# main_board.net
KiCad netlist of a schematic drawn in EAGLE
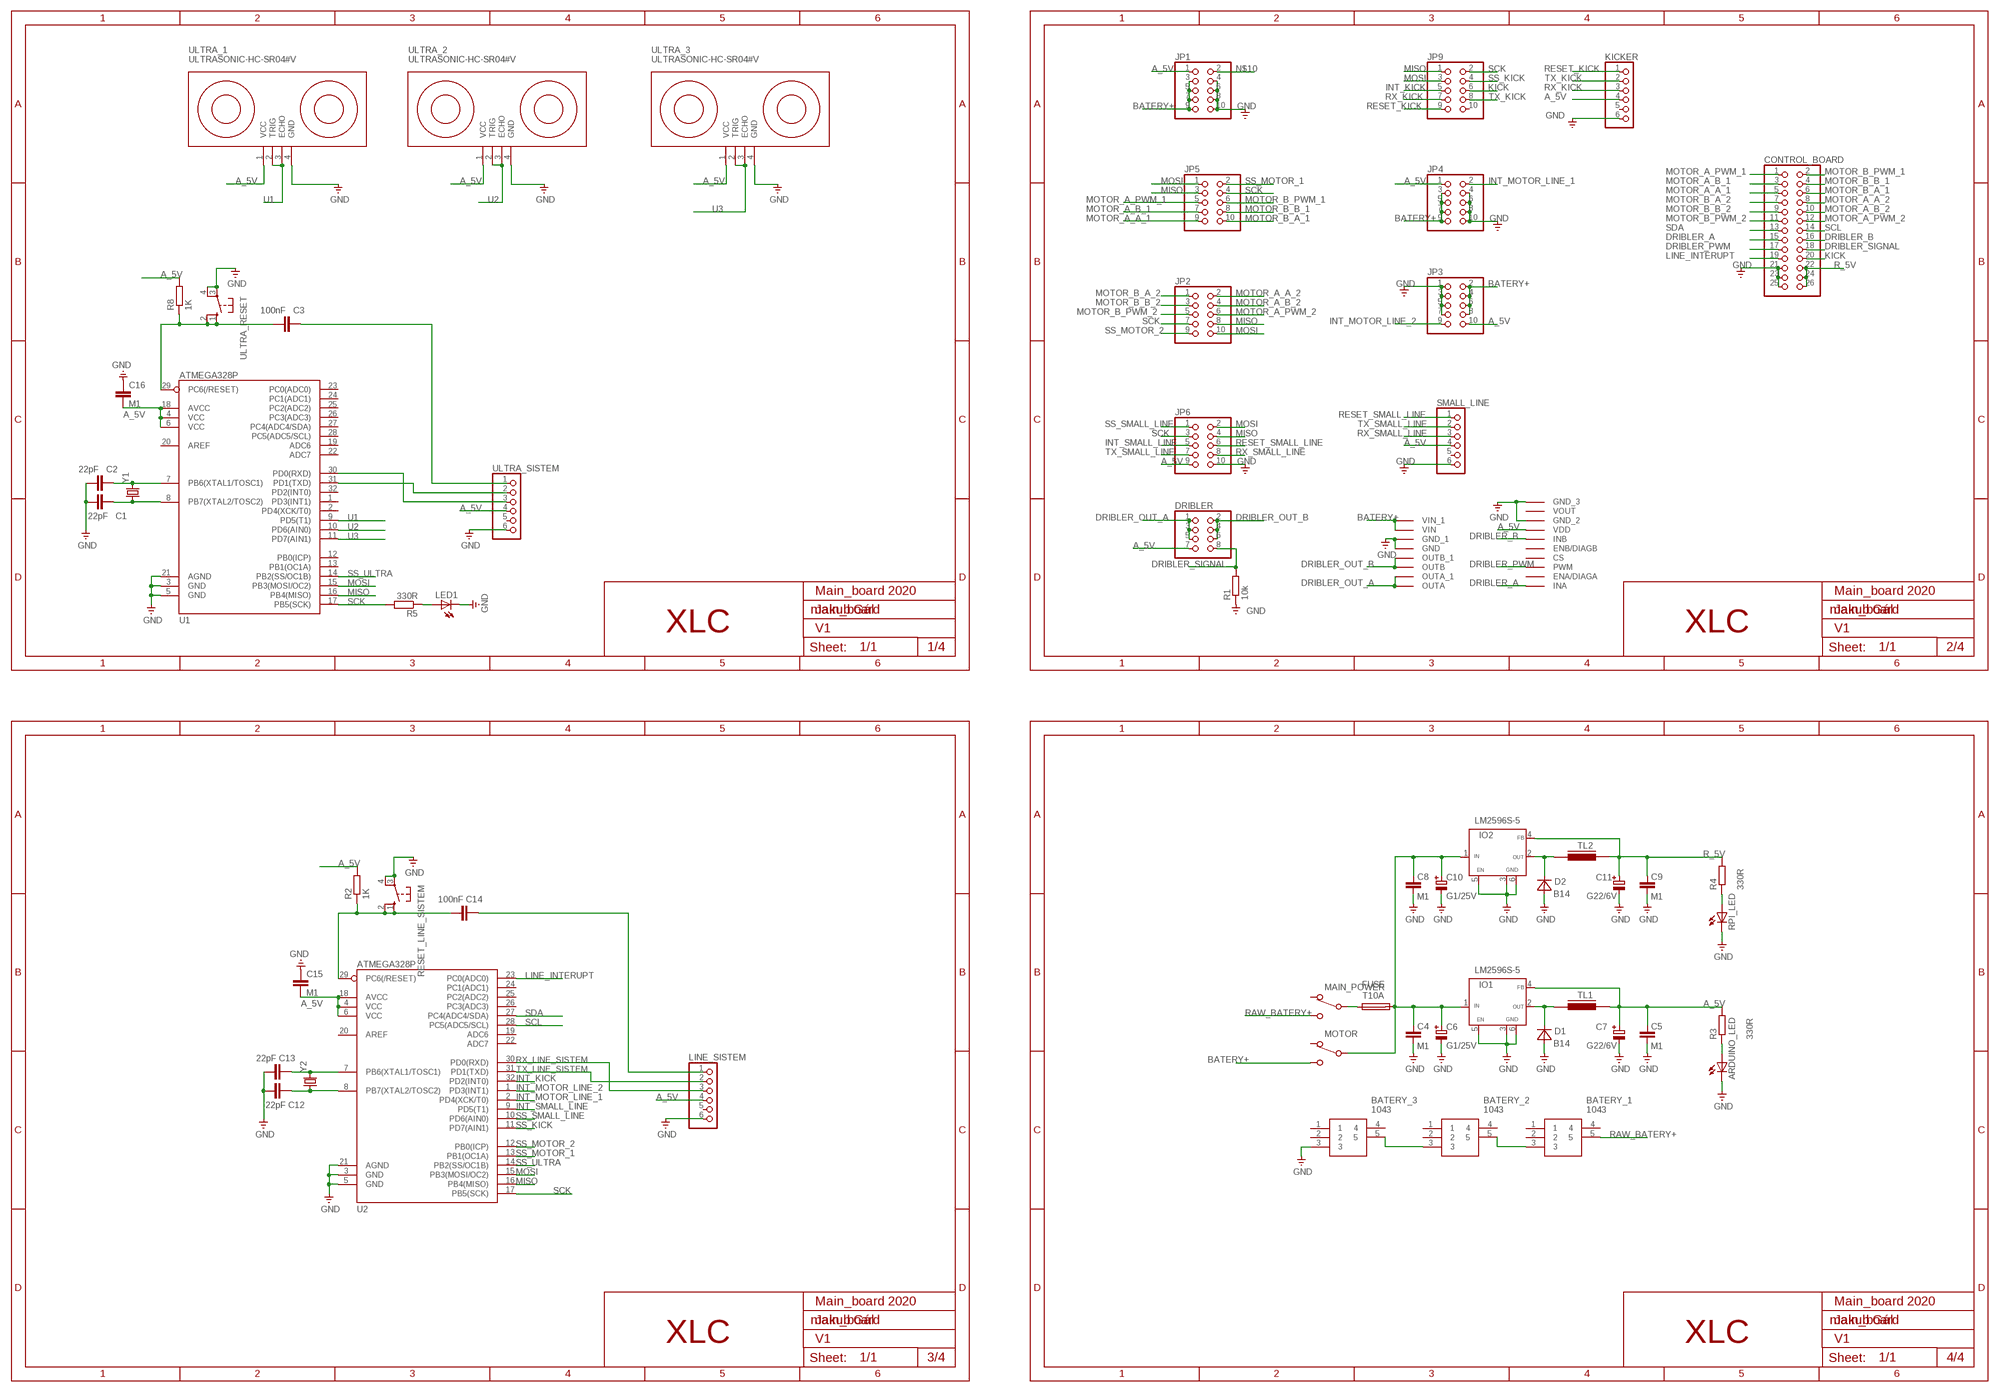
[diagram p0: schematic, sheet 1]

(export (version "E")
  (design (tool "Eeschema 10.0.6"))
  (components
    (comp (ref "ARDUINO_LED")
      (value "LEDCHIPLED_0603")
      (footprint "eagle-import:CHIPLED_0603")
      (libsource (lib "eagle-import") (part "LEDCHIPLED_0603"))
    )
    (comp (ref "BATERY_1")
      (value "1043")
      (footprint "eagle-import:1043")
      (fields (field (name "MOUSER_PART_NUMBER") "534-1043"))
      (libsource (lib "eagle-import") (part "1043"))
    )
    (comp (ref "BATERY_2")
      (value "1043")
      (footprint "eagle-import:1043")
      (fields (field (name "MOUSER_PART_NUMBER") "534-1043"))
      (libsource (lib "eagle-import") (part "1043"))
    )
    (comp (ref "BATERY_3")
      (value "1043")
      (footprint "eagle-import:1043")
      (fields (field (name "MOUSER_PART_NUMBER") "534-1043"))
      (libsource (lib "eagle-import") (part "1043"))
    )
    (comp (ref "C1")
      (value "22pF")
      (footprint "eagle-import:C0603")
      (libsource (lib "eagle-import") (part "C-EUC0603"))
    )
    (comp (ref "C2")
      (value "22pF")
      (footprint "eagle-import:C0603")
      (libsource (lib "eagle-import") (part "C-EUC0603"))
    )
    (comp (ref "C3")
      (value "100nF")
      (footprint "eagle-import:C0603")
      (libsource (lib "eagle-import") (part "C-EUC0603"))
    )
    (comp (ref "C4")
      (value "M1")
      (footprint "eagle-import:SMD-1206")
      (libsource (lib "eagle-import") (part "KOND-KERAM1206-SMD"))
    )
    (comp (ref "C5")
      (value "M1")
      (footprint "eagle-import:SMD-1206")
      (libsource (lib "eagle-import") (part "KOND-KERAM1206-SMD"))
    )
    (comp (ref "C6")
      (value "G1/25V")
      (footprint "eagle-import:SMD-ELE-D")
      (libsource (lib "eagle-import") (part "KOND-ELEKTD-SMD"))
    )
    (comp (ref "C7")
      (value "G22/6V")
      (footprint "eagle-import:SMD-ELE-D")
      (libsource (lib "eagle-import") (part "KOND-ELEKTD-SMD"))
    )
    (comp (ref "C8")
      (value "M1")
      (footprint "eagle-import:SMD-1206")
      (libsource (lib "eagle-import") (part "KOND-KERAM1206-SMD"))
    )
    (comp (ref "C9")
      (value "M1")
      (footprint "eagle-import:SMD-1206")
      (libsource (lib "eagle-import") (part "KOND-KERAM1206-SMD"))
    )
    (comp (ref "C10")
      (value "G1/25V")
      (footprint "eagle-import:SMD-ELE-D")
      (libsource (lib "eagle-import") (part "KOND-ELEKTD-SMD"))
    )
    (comp (ref "C11")
      (value "G22/6V")
      (footprint "eagle-import:SMD-ELE-D")
      (libsource (lib "eagle-import") (part "KOND-ELEKTD-SMD"))
    )
    (comp (ref "C12")
      (value "22pF")
      (footprint "eagle-import:C0603")
      (libsource (lib "eagle-import") (part "C-EUC0603"))
    )
    (comp (ref "C13")
      (value "22pF")
      (footprint "eagle-import:C0603")
      (libsource (lib "eagle-import") (part "C-EUC0603"))
    )
    (comp (ref "C14")
      (value "100nF")
      (footprint "eagle-import:C0603")
      (libsource (lib "eagle-import") (part "C-EUC0603"))
    )
    (comp (ref "C15")
      (value "M1")
      (footprint "eagle-import:C0603")
      (libsource (lib "eagle-import") (part "rcl_334_C-EUC0603"))
    )
    (comp (ref "C16")
      (value "M1")
      (footprint "eagle-import:C0603")
      (libsource (lib "eagle-import") (part "rcl_334_C-EUC0603"))
    )
    (comp (ref "CONTROL_BOARD")
      (value "PINHD-2X13_2.54")
      (footprint "eagle-import:2X13")
      (libsource (lib "eagle-import") (part "PINHD-2X13_2.54"))
    )
    (comp (ref "D1")
      (value "B14")
      (footprint "eagle-import:D-3,6X5,5")
      (libsource (lib "eagle-import") (part "DIODASMD-3,6X5,5"))
    )
    (comp (ref "D2")
      (value "B14")
      (footprint "eagle-import:D-3,6X5,5")
      (libsource (lib "eagle-import") (part "DIODASMD-3,6X5,5"))
    )
    (comp (ref "DRIBLER")
      (value "PINHD-2X4_2.54-SMD")
      (footprint "eagle-import:2X04SMD")
      (libsource (lib "eagle-import") (part "PINHD-2X4_2.54-SMD"))
    )
    (comp (ref "FUSE")
      (value "T10A")
      (footprint "eagle-import:SH22,5A")
      (libsource (lib "eagle-import") (part "POISTKA2A"))
    )
    (comp (ref "IO1")
      (value "LM2596S-5")
      (footprint "eagle-import:TO263-5")
      (libsource (lib "eagle-import") (part "LM2596S"))
    )
    (comp (ref "IO2")
      (value "LM2596S-5")
      (footprint "eagle-import:TO263-5")
      (libsource (lib "eagle-import") (part "LM2596S"))
    )
    (comp (ref "JP1")
      (value "PINHD-2X5IDC")
      (footprint "eagle-import:2X05_IDC")
      (libsource (lib "eagle-import") (part "PINHD-2X5IDC"))
    )
    (comp (ref "JP2")
      (value "PINHD-2X5IDC")
      (footprint "eagle-import:2X05_IDC")
      (libsource (lib "eagle-import") (part "PINHD-2X5IDC"))
    )
    (comp (ref "JP3")
      (value "PINHD-2X5IDC")
      (footprint "eagle-import:2X05_IDC")
      (libsource (lib "eagle-import") (part "PINHD-2X5IDC"))
    )
    (comp (ref "JP4")
      (value "PINHD-2X5IDC")
      (footprint "eagle-import:2X05_IDC")
      (libsource (lib "eagle-import") (part "PINHD-2X5IDC"))
    )
    (comp (ref "JP5")
      (value "PINHD-2X5IDC")
      (footprint "eagle-import:2X05_IDC")
      (libsource (lib "eagle-import") (part "PINHD-2X5IDC"))
    )
    (comp (ref "JP6")
      (value "PINHD-2X5IDC")
      (footprint "eagle-import:2X05_IDC")
      (libsource (lib "eagle-import") (part "PINHD-2X5IDC"))
    )
    (comp (ref "JP9")
      (value "PINHD-2X5IDC")
      (footprint "eagle-import:2X05_IDC")
      (libsource (lib "eagle-import") (part "PINHD-2X5IDC"))
    )
    (comp (ref "KICKER")
      (value "PINHD-1X6")
      (footprint "eagle-import:1X06")
      (libsource (lib "eagle-import") (part "PINHD-1X6"))
    )
    (comp (ref "LED1")
      (value "LEDCHIPLED_0603")
      (footprint "eagle-import:CHIPLED_0603")
      (libsource (lib "eagle-import") (part "LEDCHIPLED_0603"))
    )
    (comp (ref "LINE_SISTEM")
      (value "PINHD-1X6")
      (footprint "eagle-import:1X06")
      (libsource (lib "eagle-import") (part "PINHD-1X6"))
    )
    (comp (ref "MAIN_POWER")
      (value "PREP-1PB")
      (footprint "eagle-import:P-B069B")
      (libsource (lib "eagle-import") (part "PREP-1PB"))
    )
    (comp (ref "MOTOR")
      (value "PREP-1PB")
      (footprint "eagle-import:P-B069B")
      (libsource (lib "eagle-import") (part "PREP-1PB"))
    )
    (comp (ref "R1")
      (value "10k")
      (footprint "eagle-import:R0603")
      (libsource (lib "eagle-import") (part "R-EU_R0603"))
    )
    (comp (ref "R2")
      (value "1K")
      (footprint "eagle-import:R0603")
      (libsource (lib "eagle-import") (part "R-EU_R0603"))
    )
    (comp (ref "R3")
      (value "330R")
      (footprint "eagle-import:R0603")
      (libsource (lib "eagle-import") (part "R-EU_R0603"))
    )
    (comp (ref "R4")
      (value "330R")
      (footprint "eagle-import:R0603")
      (libsource (lib "eagle-import") (part "R-EU_R0603"))
    )
    (comp (ref "R5")
      (value "330R")
      (footprint "eagle-import:R0603")
      (libsource (lib "eagle-import") (part "R-EU_R0603"))
    )
    (comp (ref "R8")
      (value "1K")
      (footprint "eagle-import:R0603")
      (libsource (lib "eagle-import") (part "R-EU_R0603"))
    )
    (comp (ref "RESET_LINE_SISTEM")
      (value "10-XX")
      (footprint "eagle-import:B3F-10XX")
      (fields (field (name "MPN") "B3F-1000"))
      (libsource (lib "eagle-import") (part "10-XX"))
    )
    (comp (ref "RPI_LED")
      (value "LEDCHIPLED_0603")
      (footprint "eagle-import:CHIPLED_0603")
      (libsource (lib "eagle-import") (part "LEDCHIPLED_0603"))
    )
    (comp (ref "SMALL_LINE")
      (value "PINHD-1X6")
      (footprint "eagle-import:1X06")
      (libsource (lib "eagle-import") (part "PINHD-1X6"))
    )
    (comp (ref "TL1")
      (value "INDUK-TLSMD1")
      (footprint "eagle-import:INDUK-TL")
      (libsource (lib "eagle-import") (part "INDUK-TLSMD1"))
    )
    (comp (ref "TL2")
      (value "INDUK-TLSMD1")
      (footprint "eagle-import:INDUK-TL")
      (libsource (lib "eagle-import") (part "INDUK-TLSMD1"))
    )
    (comp (ref "U$4")
      (value "MOTOR_DRIVER")
      (footprint "eagle-import:MOTOR_DRIVER")
      (libsource (lib "eagle-import") (part "MOTOR_DRIVER"))
    )
    (comp (ref "U1")
      (value "ATMEGA328P")
      (footprint "eagle-import:TQFP32-08")
      (libsource (lib "eagle-import") (part "ATMEGA328_SMT"))
    )
    (comp (ref "U2")
      (value "ATMEGA328P")
      (footprint "eagle-import:TQFP32-08")
      (libsource (lib "eagle-import") (part "ATMEGA328_SMT"))
    )
    (comp (ref "ULTRA_1")
      (value "ULTRASONIC-HC-SR04#V")
      (footprint "eagle-import:ULTRASONIC-HC-SR04#V")
      (libsource (lib "eagle-import") (part "ULTRASONIC-HC-SR04#V"))
    )
    (comp (ref "ULTRA_2")
      (value "ULTRASONIC-HC-SR04#V")
      (footprint "eagle-import:ULTRASONIC-HC-SR04#V")
      (libsource (lib "eagle-import") (part "ULTRASONIC-HC-SR04#V"))
    )
    (comp (ref "ULTRA_3")
      (value "ULTRASONIC-HC-SR04#V")
      (footprint "eagle-import:ULTRASONIC-HC-SR04#V")
      (libsource (lib "eagle-import") (part "ULTRASONIC-HC-SR04#V"))
    )
    (comp (ref "ULTRA_RESET")
      (value "10-XX")
      (footprint "eagle-import:B3F-10XX")
      (fields (field (name "MPN") "B3F-1000"))
      (libsource (lib "eagle-import") (part "10-XX"))
    )
    (comp (ref "ULTRA_SISTEM")
      (value "PINHD-1X6")
      (footprint "eagle-import:1X06")
      (libsource (lib "eagle-import") (part "PINHD-1X6"))
    )
    (comp (ref "Y1")
      (value "CRYSTALHC49US")
      (footprint "eagle-import:HC49US")
      (libsource (lib "eagle-import") (part "CRYSTALHC49US"))
    )
    (comp (ref "Y2")
      (value "CRYSTALHC49US")
      (footprint "eagle-import:HC49US")
      (libsource (lib "eagle-import") (part "CRYSTALHC49US"))
    )
  )
  (nets
    (net (code "1") (name "/A_5V") (class "Default")
      (node (ref "C15") (pin "2") (pinfunction "2_2") (pintype "passive"))
      (node (ref "C16") (pin "2") (pinfunction "2_2") (pintype "passive"))
      (node (ref "C5") (pin "2") (pinfunction "2_2") (pintype "passive"))
      (node (ref "C7") (pin "PLUS") (pinfunction "PLUS_PLUS") (pintype "passive"))
      (node (ref "DRIBLER") (pin "7") (pinfunction "7_7") (pintype "passive"))
      (node (ref "IO1") (pin "4") (pinfunction "FB_4") (pintype "input"))
      (node (ref "JP1") (pin "1") (pinfunction "1_1") (pintype "passive"))
      (node (ref "JP3") (pin "10") (pinfunction "10_10") (pintype "passive"))
      (node (ref "JP4") (pin "1") (pinfunction "1_1") (pintype "passive"))
      (node (ref "JP6") (pin "9") (pinfunction "9_9") (pintype "passive"))
      (node (ref "KICKER") (pin "4") (pinfunction "4_4") (pintype "passive"))
      (node (ref "LINE_SISTEM") (pin "4") (pinfunction "4_4") (pintype "passive"))
      (node (ref "R2") (pin "2") (pinfunction "2_2") (pintype "passive"))
      (node (ref "R3") (pin "2") (pinfunction "2_2") (pintype "passive"))
      (node (ref "R8") (pin "2") (pinfunction "2_2") (pintype "passive"))
      (node (ref "SMALL_LINE") (pin "4") (pinfunction "4_4") (pintype "passive"))
      (node (ref "TL1") (pin "2") (pinfunction "2_2") (pintype "passive"))
      (node (ref "U$4") (pin "VDD") (pinfunction "VDD_VDD") (pintype "bidirectional"))
      (node (ref "U1") (pin "18") (pinfunction "AVCC_18") (pintype "bidirectional"))
      (node (ref "U1") (pin "4") (pinfunction "VCC_4") (pintype "bidirectional"))
      (node (ref "U1") (pin "6") (pinfunction "VCC_6") (pintype "bidirectional"))
      (node (ref "U2") (pin "18") (pinfunction "AVCC_18") (pintype "bidirectional"))
      (node (ref "U2") (pin "4") (pinfunction "VCC_4") (pintype "bidirectional"))
      (node (ref "U2") (pin "6") (pinfunction "VCC_6") (pintype "bidirectional"))
      (node (ref "ULTRA_1") (pin "1") (pinfunction "VCC_1") (pintype "power_in"))
      (node (ref "ULTRA_2") (pin "1") (pinfunction "VCC_1") (pintype "power_in"))
      (node (ref "ULTRA_3") (pin "1") (pinfunction "VCC_1") (pintype "power_in"))
      (node (ref "ULTRA_SISTEM") (pin "4") (pinfunction "4_4") (pintype "passive"))
    )
    (net (code "2") (name "/BATERY+") (class "Default")
      (node (ref "JP1") (pin "3") (pinfunction "3_3") (pintype "passive"))
      (node (ref "JP1") (pin "5") (pinfunction "5_5") (pintype "passive"))
      (node (ref "JP1") (pin "7") (pinfunction "7_7") (pintype "passive"))
      (node (ref "JP1") (pin "9") (pinfunction "9_9") (pintype "passive"))
      (node (ref "JP3") (pin "2") (pinfunction "2_2") (pintype "passive"))
      (node (ref "JP3") (pin "4") (pinfunction "4_4") (pintype "passive"))
      (node (ref "JP3") (pin "6") (pinfunction "6_6") (pintype "passive"))
      (node (ref "JP3") (pin "8") (pinfunction "8_8") (pintype "passive"))
      (node (ref "JP4") (pin "3") (pinfunction "3_3") (pintype "passive"))
      (node (ref "JP4") (pin "5") (pinfunction "5_5") (pintype "passive"))
      (node (ref "JP4") (pin "7") (pinfunction "7_7") (pintype "passive"))
      (node (ref "JP4") (pin "9") (pinfunction "9_9") (pintype "passive"))
      (node (ref "MOTOR") (pin "1") (pinfunction "1-OFF_1") (pintype "passive"))
      (node (ref "U$4") (pin "VIN") (pinfunction "VIN_VIN") (pintype "bidirectional"))
      (node (ref "U$4") (pin "VIN_1") (pinfunction "VIN_1_VIN_1") (pintype "bidirectional"))
    )
    (net (code "3") (name "/DRIBLER_A") (class "Default")
      (node (ref "CONTROL_BOARD") (pin "15") (pinfunction "15_15") (pintype "passive"))
      (node (ref "U$4") (pin "INA") (pinfunction "INA_INA") (pintype "bidirectional"))
    )
    (net (code "4") (name "/DRIBLER_B") (class "Default")
      (node (ref "CONTROL_BOARD") (pin "16") (pinfunction "16_16") (pintype "passive"))
      (node (ref "U$4") (pin "INB") (pinfunction "INB_INB") (pintype "bidirectional"))
    )
    (net (code "5") (name "/DRIBLER_OUT_A") (class "Default")
      (node (ref "DRIBLER") (pin "1") (pinfunction "1_1") (pintype "passive"))
      (node (ref "DRIBLER") (pin "3") (pinfunction "3_3") (pintype "passive"))
      (node (ref "DRIBLER") (pin "5") (pinfunction "5_5") (pintype "passive"))
      (node (ref "U$4") (pin "OUTA") (pinfunction "OUTA_OUTA") (pintype "bidirectional"))
      (node (ref "U$4") (pin "OUTA_1") (pinfunction "OUTA_1_OUTA_1") (pintype "bidirectional"))
    )
    (net (code "6") (name "/DRIBLER_OUT_B") (class "Default")
      (node (ref "DRIBLER") (pin "2") (pinfunction "2_2") (pintype "passive"))
      (node (ref "DRIBLER") (pin "4") (pinfunction "4_4") (pintype "passive"))
      (node (ref "DRIBLER") (pin "6") (pinfunction "6_6") (pintype "passive"))
      (node (ref "U$4") (pin "OUTB") (pinfunction "OUTB_OUTB") (pintype "bidirectional"))
      (node (ref "U$4") (pin "OUTB_1") (pinfunction "OUTB_1_OUTB_1") (pintype "bidirectional"))
    )
    (net (code "7") (name "/DRIBLER_PWM") (class "Default")
      (node (ref "CONTROL_BOARD") (pin "17") (pinfunction "17_17") (pintype "passive"))
      (node (ref "U$4") (pin "PWM") (pinfunction "PWM_PWM") (pintype "bidirectional"))
    )
    (net (code "8") (name "/DRIBLER_SIGNAL") (class "Default")
      (node (ref "CONTROL_BOARD") (pin "18") (pinfunction "18_18") (pintype "passive"))
      (node (ref "DRIBLER") (pin "8") (pinfunction "8_8") (pintype "passive"))
      (node (ref "R1") (pin "2") (pinfunction "2_2") (pintype "passive"))
    )
    (net (code "9") (name "/INT_KICK") (class "Default")
      (node (ref "JP9") (pin "5") (pinfunction "5_5") (pintype "passive"))
      (node (ref "U2") (pin "32") (pinfunction "PD2(INT0)_32") (pintype "bidirectional"))
    )
    (net (code "10") (name "/INT_MOTOR_LINE_1") (class "Default")
      (node (ref "JP4") (pin "2") (pinfunction "2_2") (pintype "passive"))
      (node (ref "U2") (pin "2") (pinfunction "PD4(XCK/T0)_2") (pintype "bidirectional"))
    )
    (net (code "11") (name "/INT_MOTOR_LINE_2") (class "Default")
      (node (ref "JP3") (pin "9") (pinfunction "9_9") (pintype "passive"))
      (node (ref "U2") (pin "1") (pinfunction "PD3(INT1)_1") (pintype "bidirectional"))
    )
    (net (code "12") (name "/INT_SMALL_LINE") (class "Default")
      (node (ref "JP6") (pin "5") (pinfunction "5_5") (pintype "passive"))
      (node (ref "U2") (pin "9") (pinfunction "PD5(T1)_9") (pintype "bidirectional"))
    )
    (net (code "13") (name "/KICK") (class "Default")
      (node (ref "CONTROL_BOARD") (pin "20") (pinfunction "20_20") (pintype "passive"))
      (node (ref "JP9") (pin "6") (pinfunction "6_6") (pintype "passive"))
    )
    (net (code "14") (name "/LINE_INTERUPT") (class "Default")
      (node (ref "CONTROL_BOARD") (pin "19") (pinfunction "19_19") (pintype "passive"))
      (node (ref "U2") (pin "23") (pinfunction "PC0(ADC0)_23") (pintype "bidirectional"))
    )
    (net (code "15") (name "/MISO") (class "Default")
      (node (ref "JP2") (pin "8") (pinfunction "8_8") (pintype "passive"))
      (node (ref "JP5") (pin "3") (pinfunction "3_3") (pintype "passive"))
      (node (ref "JP6") (pin "4") (pinfunction "4_4") (pintype "passive"))
      (node (ref "JP9") (pin "1") (pinfunction "1_1") (pintype "passive"))
      (node (ref "U1") (pin "16") (pinfunction "PB4(MISO)_16") (pintype "bidirectional"))
      (node (ref "U2") (pin "16") (pinfunction "PB4(MISO)_16") (pintype "bidirectional"))
    )
    (net (code "16") (name "/MOSI") (class "Default")
      (node (ref "JP2") (pin "10") (pinfunction "10_10") (pintype "passive"))
      (node (ref "JP5") (pin "1") (pinfunction "1_1") (pintype "passive"))
      (node (ref "JP6") (pin "2") (pinfunction "2_2") (pintype "passive"))
      (node (ref "JP9") (pin "3") (pinfunction "3_3") (pintype "passive"))
      (node (ref "U1") (pin "15") (pinfunction "PB3(MOSI/OC2)_15") (pintype "bidirectional"))
      (node (ref "U2") (pin "15") (pinfunction "PB3(MOSI/OC2)_15") (pintype "bidirectional"))
    )
    (net (code "17") (name "/MOTOR_A_A_1") (class "Default")
      (node (ref "CONTROL_BOARD") (pin "5") (pinfunction "5_5") (pintype "passive"))
      (node (ref "JP5") (pin "9") (pinfunction "9_9") (pintype "passive"))
    )
    (net (code "18") (name "/MOTOR_A_A_2") (class "Default")
      (node (ref "CONTROL_BOARD") (pin "8") (pinfunction "8_8") (pintype "passive"))
      (node (ref "JP2") (pin "2") (pinfunction "2_2") (pintype "passive"))
    )
    (net (code "19") (name "/MOTOR_A_B_1") (class "Default")
      (node (ref "CONTROL_BOARD") (pin "3") (pinfunction "3_3") (pintype "passive"))
      (node (ref "JP5") (pin "7") (pinfunction "7_7") (pintype "passive"))
    )
    (net (code "20") (name "/MOTOR_A_B_2") (class "Default")
      (node (ref "CONTROL_BOARD") (pin "10") (pinfunction "10_10") (pintype "passive"))
      (node (ref "JP2") (pin "4") (pinfunction "4_4") (pintype "passive"))
    )
    (net (code "21") (name "/MOTOR_A_PWM_1") (class "Default")
      (node (ref "CONTROL_BOARD") (pin "1") (pinfunction "1_1") (pintype "passive"))
      (node (ref "JP5") (pin "5") (pinfunction "5_5") (pintype "passive"))
    )
    (net (code "22") (name "/MOTOR_A_PWM_2") (class "Default")
      (node (ref "CONTROL_BOARD") (pin "12") (pinfunction "12_12") (pintype "passive"))
      (node (ref "JP2") (pin "6") (pinfunction "6_6") (pintype "passive"))
    )
    (net (code "23") (name "/MOTOR_B_A_1") (class "Default")
      (node (ref "CONTROL_BOARD") (pin "6") (pinfunction "6_6") (pintype "passive"))
      (node (ref "JP5") (pin "10") (pinfunction "10_10") (pintype "passive"))
    )
    (net (code "24") (name "/MOTOR_B_A_2") (class "Default")
      (node (ref "CONTROL_BOARD") (pin "7") (pinfunction "7_7") (pintype "passive"))
      (node (ref "JP2") (pin "1") (pinfunction "1_1") (pintype "passive"))
    )
    (net (code "25") (name "/MOTOR_B_B_1") (class "Default")
      (node (ref "CONTROL_BOARD") (pin "4") (pinfunction "4_4") (pintype "passive"))
      (node (ref "JP5") (pin "8") (pinfunction "8_8") (pintype "passive"))
    )
    (net (code "26") (name "/MOTOR_B_B_2") (class "Default")
      (node (ref "CONTROL_BOARD") (pin "9") (pinfunction "9_9") (pintype "passive"))
      (node (ref "JP2") (pin "3") (pinfunction "3_3") (pintype "passive"))
    )
    (net (code "27") (name "/MOTOR_B_PWM_1") (class "Default")
      (node (ref "CONTROL_BOARD") (pin "2") (pinfunction "2_2") (pintype "passive"))
      (node (ref "JP5") (pin "6") (pinfunction "6_6") (pintype "passive"))
    )
    (net (code "28") (name "/MOTOR_B_PWM_2") (class "Default")
      (node (ref "CONTROL_BOARD") (pin "11") (pinfunction "11_11") (pintype "passive"))
      (node (ref "JP2") (pin "5") (pinfunction "5_5") (pintype "passive"))
    )
    (net (code "29") (name "/N$10") (class "Default")
      (node (ref "JP1") (pin "2") (pinfunction "2_2") (pintype "passive"))
    )
    (net (code "30") (name "/RAW_BATERY+") (class "Default")
      (node (ref "BATERY_1") (pin "5") (pinfunction "5_5") (pintype "bidirectional"))
      (node (ref "MAIN_POWER") (pin "1") (pinfunction "1-OFF_1") (pintype "passive"))
    )
    (net (code "31") (name "/RESET_KICK") (class "Default")
      (node (ref "JP9") (pin "9") (pinfunction "9_9") (pintype "passive"))
      (node (ref "KICKER") (pin "1") (pinfunction "1_1") (pintype "passive"))
    )
    (net (code "32") (name "/RESET_SMALL_LINE") (class "Default")
      (node (ref "JP6") (pin "6") (pinfunction "6_6") (pintype "passive"))
      (node (ref "SMALL_LINE") (pin "1") (pinfunction "1_1") (pintype "passive"))
    )
    (net (code "33") (name "/RX_KICK") (class "Default")
      (node (ref "JP9") (pin "7") (pinfunction "7_7") (pintype "passive"))
      (node (ref "KICKER") (pin "3") (pinfunction "3_3") (pintype "passive"))
    )
    (net (code "34") (name "/RX_LINE_SISTEM") (class "Default")
      (node (ref "LINE_SISTEM") (pin "3") (pinfunction "3_3") (pintype "passive"))
      (node (ref "U2") (pin "30") (pinfunction "PD0(RXD)_30") (pintype "bidirectional"))
    )
    (net (code "35") (name "/RX_SMALL_LINE") (class "Default")
      (node (ref "JP6") (pin "8") (pinfunction "8_8") (pintype "passive"))
      (node (ref "SMALL_LINE") (pin "3") (pinfunction "3_3") (pintype "passive"))
    )
    (net (code "36") (name "/R_5V") (class "Default")
      (node (ref "C11") (pin "PLUS") (pinfunction "PLUS_PLUS") (pintype "passive"))
      (node (ref "C9") (pin "2") (pinfunction "2_2") (pintype "passive"))
      (node (ref "CONTROL_BOARD") (pin "22") (pinfunction "22_22") (pintype "passive"))
      (node (ref "CONTROL_BOARD") (pin "24") (pinfunction "24_24") (pintype "passive"))
      (node (ref "CONTROL_BOARD") (pin "26") (pinfunction "26_26") (pintype "passive"))
      (node (ref "IO2") (pin "4") (pinfunction "FB_4") (pintype "input"))
      (node (ref "R4") (pin "2") (pinfunction "2_2") (pintype "passive"))
      (node (ref "TL2") (pin "2") (pinfunction "2_2") (pintype "passive"))
    )
    (net (code "37") (name "/SCK") (class "Default")
      (node (ref "JP2") (pin "7") (pinfunction "7_7") (pintype "passive"))
      (node (ref "JP5") (pin "4") (pinfunction "4_4") (pintype "passive"))
      (node (ref "JP6") (pin "3") (pinfunction "3_3") (pintype "passive"))
      (node (ref "JP9") (pin "2") (pinfunction "2_2") (pintype "passive"))
      (node (ref "R5") (pin "2") (pinfunction "2_2") (pintype "passive"))
      (node (ref "U1") (pin "17") (pinfunction "PB5(SCK)_17") (pintype "bidirectional"))
      (node (ref "U2") (pin "17") (pinfunction "PB5(SCK)_17") (pintype "bidirectional"))
    )
    (net (code "38") (name "/SCL") (class "Default")
      (node (ref "CONTROL_BOARD") (pin "14") (pinfunction "14_14") (pintype "passive"))
      (node (ref "U2") (pin "28") (pinfunction "PC5(ADC5/SCL)_28") (pintype "bidirectional"))
    )
    (net (code "39") (name "/SDA") (class "Default")
      (node (ref "CONTROL_BOARD") (pin "13") (pinfunction "13_13") (pintype "passive"))
      (node (ref "U2") (pin "27") (pinfunction "PC4(ADC4/SDA)_27") (pintype "bidirectional"))
    )
    (net (code "40") (name "/SS_KICK") (class "Default")
      (node (ref "JP9") (pin "4") (pinfunction "4_4") (pintype "passive"))
      (node (ref "U2") (pin "11") (pinfunction "PD7(AIN1)_11") (pintype "bidirectional"))
    )
    (net (code "41") (name "/SS_MOTOR_1") (class "Default")
      (node (ref "JP5") (pin "2") (pinfunction "2_2") (pintype "passive"))
      (node (ref "U2") (pin "13") (pinfunction "PB1(OC1A)_13") (pintype "bidirectional"))
    )
    (net (code "42") (name "/SS_MOTOR_2") (class "Default")
      (node (ref "JP2") (pin "9") (pinfunction "9_9") (pintype "passive"))
      (node (ref "U2") (pin "12") (pinfunction "PB0(ICP)_12") (pintype "bidirectional"))
    )
    (net (code "43") (name "/SS_SMALL_LINE") (class "Default")
      (node (ref "JP6") (pin "1") (pinfunction "1_1") (pintype "passive"))
      (node (ref "U2") (pin "10") (pinfunction "PD6(AIN0)_10") (pintype "bidirectional"))
    )
    (net (code "44") (name "/SS_ULTRA") (class "Default")
      (node (ref "U1") (pin "14") (pinfunction "PB2(SS/OC1B)_14") (pintype "bidirectional"))
      (node (ref "U2") (pin "14") (pinfunction "PB2(SS/OC1B)_14") (pintype "bidirectional"))
    )
    (net (code "45") (name "/TX_KICK") (class "Default")
      (node (ref "JP9") (pin "8") (pinfunction "8_8") (pintype "passive"))
      (node (ref "KICKER") (pin "2") (pinfunction "2_2") (pintype "passive"))
    )
    (net (code "46") (name "/TX_LINE_SISTEM") (class "Default")
      (node (ref "LINE_SISTEM") (pin "2") (pinfunction "2_2") (pintype "passive"))
      (node (ref "U2") (pin "31") (pinfunction "PD1(TXD)_31") (pintype "bidirectional"))
    )
    (net (code "47") (name "/TX_SMALL_LINE") (class "Default")
      (node (ref "JP6") (pin "7") (pinfunction "7_7") (pintype "passive"))
      (node (ref "SMALL_LINE") (pin "2") (pinfunction "2_2") (pintype "passive"))
    )
    (net (code "48") (name "/U1") (class "Default")
      (node (ref "U1") (pin "9") (pinfunction "PD5(T1)_9") (pintype "bidirectional"))
      (node (ref "ULTRA_1") (pin "2") (pinfunction "TRIG_2") (pintype "input"))
      (node (ref "ULTRA_1") (pin "3") (pinfunction "ECHO_3") (pintype "output"))
    )
    (net (code "49") (name "/U2") (class "Default")
      (node (ref "U1") (pin "10") (pinfunction "PD6(AIN0)_10") (pintype "bidirectional"))
      (node (ref "ULTRA_2") (pin "2") (pinfunction "TRIG_2") (pintype "input"))
      (node (ref "ULTRA_2") (pin "3") (pinfunction "ECHO_3") (pintype "output"))
    )
    (net (code "50") (name "/U3") (class "Default")
      (node (ref "U1") (pin "11") (pinfunction "PD7(AIN1)_11") (pintype "bidirectional"))
      (node (ref "ULTRA_3") (pin "2") (pinfunction "TRIG_2") (pintype "input"))
      (node (ref "ULTRA_3") (pin "3") (pinfunction "ECHO_3") (pintype "output"))
    )
    (net (code "51") (name "GND") (class "Default")
      (node (ref "ARDUINO_LED") (pin "C") (pinfunction "C_C") (pintype "passive"))
      (node (ref "BATERY_3") (pin "3") (pinfunction "3_3") (pintype "bidirectional"))
      (node (ref "C1") (pin "1") (pinfunction "1_1") (pintype "passive"))
      (node (ref "C10") (pin "MINUS") (pinfunction "MINUS_MINUS") (pintype "passive"))
      (node (ref "C11") (pin "MINUS") (pinfunction "MINUS_MINUS") (pintype "passive"))
      (node (ref "C12") (pin "1") (pinfunction "1_1") (pintype "passive"))
      (node (ref "C13") (pin "1") (pinfunction "1_1") (pintype "passive"))
      (node (ref "C15") (pin "1") (pinfunction "1_1") (pintype "passive"))
      (node (ref "C16") (pin "1") (pinfunction "1_1") (pintype "passive"))
      (node (ref "C2") (pin "1") (pinfunction "1_1") (pintype "passive"))
      (node (ref "C4") (pin "1") (pinfunction "1_1") (pintype "passive"))
      (node (ref "C5") (pin "1") (pinfunction "1_1") (pintype "passive"))
      (node (ref "C6") (pin "MINUS") (pinfunction "MINUS_MINUS") (pintype "passive"))
      (node (ref "C7") (pin "MINUS") (pinfunction "MINUS_MINUS") (pintype "passive"))
      (node (ref "C8") (pin "1") (pinfunction "1_1") (pintype "passive"))
      (node (ref "C9") (pin "1") (pinfunction "1_1") (pintype "passive"))
      (node (ref "CONTROL_BOARD") (pin "21") (pinfunction "21_21") (pintype "passive"))
      (node (ref "CONTROL_BOARD") (pin "23") (pinfunction "23_23") (pintype "passive"))
      (node (ref "CONTROL_BOARD") (pin "25") (pinfunction "25_25") (pintype "passive"))
      (node (ref "D1") (pin "A") (pinfunction "A_A") (pintype "passive"))
      (node (ref "D2") (pin "A") (pinfunction "A_A") (pintype "passive"))
      (node (ref "IO1") (pin "3") (pinfunction "GND_3") (pintype "power_in"))
      (node (ref "IO1") (pin "5") (pinfunction "EN_5") (pintype "input"))
      (node (ref "IO1") (pin "6") (pinfunction "GND_6") (pintype "power_in"))
      (node (ref "IO2") (pin "3") (pinfunction "GND_3") (pintype "power_in"))
      (node (ref "IO2") (pin "5") (pinfunction "EN_5") (pintype "input"))
      (node (ref "IO2") (pin "6") (pinfunction "GND_6") (pintype "power_in"))
      (node (ref "JP1") (pin "10") (pinfunction "10_10") (pintype "passive"))
      (node (ref "JP1") (pin "4") (pinfunction "4_4") (pintype "passive"))
      (node (ref "JP1") (pin "6") (pinfunction "6_6") (pintype "passive"))
      (node (ref "JP1") (pin "8") (pinfunction "8_8") (pintype "passive"))
      (node (ref "JP3") (pin "1") (pinfunction "1_1") (pintype "passive"))
      (node (ref "JP3") (pin "3") (pinfunction "3_3") (pintype "passive"))
      (node (ref "JP3") (pin "5") (pinfunction "5_5") (pintype "passive"))
      (node (ref "JP3") (pin "7") (pinfunction "7_7") (pintype "passive"))
      (node (ref "JP4") (pin "10") (pinfunction "10_10") (pintype "passive"))
      (node (ref "JP4") (pin "4") (pinfunction "4_4") (pintype "passive"))
      (node (ref "JP4") (pin "6") (pinfunction "6_6") (pintype "passive"))
      (node (ref "JP4") (pin "8") (pinfunction "8_8") (pintype "passive"))
      (node (ref "JP6") (pin "10") (pinfunction "10_10") (pintype "passive"))
      (node (ref "KICKER") (pin "6") (pinfunction "6_6") (pintype "passive"))
      (node (ref "LED1") (pin "C") (pinfunction "C_C") (pintype "passive"))
      (node (ref "LINE_SISTEM") (pin "6") (pinfunction "6_6") (pintype "passive"))
      (node (ref "R1") (pin "1") (pinfunction "1_1") (pintype "passive"))
      (node (ref "RESET_LINE_SISTEM") (pin "3") (pinfunction "P_3") (pintype "passive"))
      (node (ref "RESET_LINE_SISTEM") (pin "4") (pinfunction "P1_4") (pintype "passive"))
      (node (ref "RPI_LED") (pin "C") (pinfunction "C_C") (pintype "passive"))
      (node (ref "SMALL_LINE") (pin "6") (pinfunction "6_6") (pintype "passive"))
      (node (ref "U$4") (pin "GND") (pinfunction "GND_GND") (pintype "bidirectional"))
      (node (ref "U$4") (pin "GND_1") (pinfunction "GND_1_GND_1") (pintype "bidirectional"))
      (node (ref "U$4") (pin "GND_2") (pinfunction "GND_2_GND_2") (pintype "bidirectional"))
      (node (ref "U$4") (pin "GND_3") (pinfunction "GND_3_GND_3") (pintype "bidirectional"))
      (node (ref "U1") (pin "21") (pinfunction "AGND_21") (pintype "bidirectional"))
      (node (ref "U1") (pin "3") (pinfunction "GND_3") (pintype "bidirectional"))
      (node (ref "U1") (pin "5") (pinfunction "GND_5") (pintype "bidirectional"))
      (node (ref "U2") (pin "21") (pinfunction "AGND_21") (pintype "bidirectional"))
      (node (ref "U2") (pin "3") (pinfunction "GND_3") (pintype "bidirectional"))
      (node (ref "U2") (pin "5") (pinfunction "GND_5") (pintype "bidirectional"))
      (node (ref "ULTRA_1") (pin "4") (pinfunction "GND_4") (pintype "power_in"))
      (node (ref "ULTRA_2") (pin "4") (pinfunction "GND_4") (pintype "power_in"))
      (node (ref "ULTRA_3") (pin "4") (pinfunction "GND_4") (pintype "power_in"))
      (node (ref "ULTRA_RESET") (pin "3") (pinfunction "P_3") (pintype "passive"))
      (node (ref "ULTRA_RESET") (pin "4") (pinfunction "P1_4") (pintype "passive"))
      (node (ref "ULTRA_SISTEM") (pin "6") (pinfunction "6_6") (pintype "passive"))
    )
    (net (code "52") (name "Net-(ARDUINO_LED-PadA)") (class "Default")
      (node (ref "ARDUINO_LED") (pin "A") (pinfunction "A_A") (pintype "passive"))
      (node (ref "R3") (pin "1") (pinfunction "1_1") (pintype "passive"))
    )
    (net (code "53") (name "Net-(BATERY_1-Pad3)") (class "Default")
      (node (ref "BATERY_1") (pin "3") (pinfunction "3_3") (pintype "bidirectional"))
      (node (ref "BATERY_2") (pin "5") (pinfunction "5_5") (pintype "bidirectional"))
    )
    (net (code "54") (name "Net-(BATERY_2-Pad3)") (class "Default")
      (node (ref "BATERY_2") (pin "3") (pinfunction "3_3") (pintype "bidirectional"))
      (node (ref "BATERY_3") (pin "5") (pinfunction "5_5") (pintype "bidirectional"))
    )
    (net (code "55") (name "Net-(C3-Pad2)") (class "Default")
      (node (ref "C3") (pin "2") (pinfunction "2_2") (pintype "passive"))
      (node (ref "ULTRA_SISTEM") (pin "1") (pinfunction "1_1") (pintype "passive"))
    )
    (net (code "56") (name "Net-(C14-Pad2)") (class "Default")
      (node (ref "C14") (pin "2") (pinfunction "2_2") (pintype "passive"))
      (node (ref "LINE_SISTEM") (pin "1") (pinfunction "1_1") (pintype "passive"))
    )
    (net (code "57") (name "Net-(IO1-IN)") (class "Default")
      (node (ref "C10") (pin "PLUS") (pinfunction "PLUS_PLUS") (pintype "passive"))
      (node (ref "C4") (pin "2") (pinfunction "2_2") (pintype "passive"))
      (node (ref "C6") (pin "PLUS") (pinfunction "PLUS_PLUS") (pintype "passive"))
      (node (ref "C8") (pin "2") (pinfunction "2_2") (pintype "passive"))
      (node (ref "FUSE") (pin "2") (pinfunction "2_2") (pintype "passive"))
      (node (ref "IO1") (pin "1") (pinfunction "IN_1") (pintype "input"))
      (node (ref "IO2") (pin "1") (pinfunction "IN_1") (pintype "input"))
      (node (ref "MOTOR") (pin "2") (pinfunction "2-COM_2") (pintype "passive"))
    )
    (net (code "58") (name "Net-(IO1-OUT)") (class "Default")
      (node (ref "D1") (pin "K") (pinfunction "K_K") (pintype "passive"))
      (node (ref "IO1") (pin "2") (pinfunction "OUT_2") (pintype "output"))
      (node (ref "TL1") (pin "1") (pinfunction "1_1") (pintype "passive"))
    )
    (net (code "59") (name "Net-(IO2-OUT)") (class "Default")
      (node (ref "D2") (pin "K") (pinfunction "K_K") (pintype "passive"))
      (node (ref "IO2") (pin "2") (pinfunction "OUT_2") (pintype "output"))
      (node (ref "TL2") (pin "1") (pinfunction "1_1") (pintype "passive"))
    )
    (net (code "60") (name "Net-(LED1-PadA)") (class "Default")
      (node (ref "LED1") (pin "A") (pinfunction "A_A") (pintype "passive"))
      (node (ref "R5") (pin "1") (pinfunction "1_1") (pintype "passive"))
    )
    (net (code "61") (name "Net-(MAIN_POWER-2-COM)") (class "Default")
      (node (ref "FUSE") (pin "1") (pinfunction "1_1") (pintype "passive"))
      (node (ref "MAIN_POWER") (pin "2") (pinfunction "2-COM_2") (pintype "passive"))
    )
    (net (code "62") (name "Net-(R4-Pad1)") (class "Default")
      (node (ref "R4") (pin "1") (pinfunction "1_1") (pintype "passive"))
      (node (ref "RPI_LED") (pin "A") (pinfunction "A_A") (pintype "passive"))
    )
    (net (code "63") (name "Net-(RESET_LINE_SISTEM-S)") (class "Default")
      (node (ref "C14") (pin "1") (pinfunction "1_1") (pintype "passive"))
      (node (ref "R2") (pin "1") (pinfunction "1_1") (pintype "passive"))
      (node (ref "RESET_LINE_SISTEM") (pin "1") (pinfunction "S_1") (pintype "passive"))
      (node (ref "RESET_LINE_SISTEM") (pin "2") (pinfunction "S1_2") (pintype "passive"))
      (node (ref "U2") (pin "29") (pinfunction "PC6(/RESET)_29") (pintype "bidirectional"))
    )
    (net (code "64") (name "Net-(U1-PB6(XTAL1{slash}TOSC1))") (class "Default")
      (node (ref "C2") (pin "2") (pinfunction "2_2") (pintype "passive"))
      (node (ref "U1") (pin "7") (pinfunction "PB6(XTAL1/TOSC1)_7") (pintype "bidirectional"))
      (node (ref "Y1") (pin "2") (pinfunction "2_2") (pintype "passive"))
    )
    (net (code "65") (name "Net-(U1-PB7(XTAL2{slash}TOSC2))") (class "Default")
      (node (ref "C1") (pin "2") (pinfunction "2_2") (pintype "passive"))
      (node (ref "U1") (pin "8") (pinfunction "PB7(XTAL2/TOSC2)_8") (pintype "bidirectional"))
      (node (ref "Y1") (pin "1") (pinfunction "1_1") (pintype "passive"))
    )
    (net (code "66") (name "Net-(U1-PC6({slash}RESET))") (class "Default")
      (node (ref "C3") (pin "1") (pinfunction "1_1") (pintype "passive"))
      (node (ref "R8") (pin "1") (pinfunction "1_1") (pintype "passive"))
      (node (ref "U1") (pin "29") (pinfunction "PC6(/RESET)_29") (pintype "bidirectional"))
      (node (ref "ULTRA_RESET") (pin "1") (pinfunction "S_1") (pintype "passive"))
      (node (ref "ULTRA_RESET") (pin "2") (pinfunction "S1_2") (pintype "passive"))
    )
    (net (code "67") (name "Net-(U1-PD0(RXD))") (class "Default")
      (node (ref "U1") (pin "30") (pinfunction "PD0(RXD)_30") (pintype "bidirectional"))
      (node (ref "ULTRA_SISTEM") (pin "3") (pinfunction "3_3") (pintype "passive"))
    )
    (net (code "68") (name "Net-(U1-PD1(TXD))") (class "Default")
      (node (ref "U1") (pin "31") (pinfunction "PD1(TXD)_31") (pintype "bidirectional"))
      (node (ref "ULTRA_SISTEM") (pin "2") (pinfunction "2_2") (pintype "passive"))
    )
    (net (code "69") (name "Net-(U2-PB6(XTAL1{slash}TOSC1))") (class "Default")
      (node (ref "C13") (pin "2") (pinfunction "2_2") (pintype "passive"))
      (node (ref "U2") (pin "7") (pinfunction "PB6(XTAL1/TOSC1)_7") (pintype "bidirectional"))
      (node (ref "Y2") (pin "2") (pinfunction "2_2") (pintype "passive"))
    )
    (net (code "70") (name "Net-(U2-PB7(XTAL2{slash}TOSC2))") (class "Default")
      (node (ref "C12") (pin "2") (pinfunction "2_2") (pintype "passive"))
      (node (ref "U2") (pin "8") (pinfunction "PB7(XTAL2/TOSC2)_8") (pintype "bidirectional"))
      (node (ref "Y2") (pin "1") (pinfunction "1_1") (pintype "passive"))
    )
    (net (code "71") (name "unconnected-(BATERY_1-Pad1)") (class "Default")
      (node (ref "BATERY_1") (pin "1") (pinfunction "1_1") (pintype "bidirectional"))
    )
    (net (code "72") (name "unconnected-(BATERY_1-Pad2)") (class "Default")
      (node (ref "BATERY_1") (pin "2") (pinfunction "2_2") (pintype "bidirectional"))
    )
    (net (code "73") (name "unconnected-(BATERY_1-Pad4)") (class "Default")
      (node (ref "BATERY_1") (pin "4") (pinfunction "4_4") (pintype "bidirectional"))
    )
    (net (code "74") (name "unconnected-(BATERY_2-Pad1)") (class "Default")
      (node (ref "BATERY_2") (pin "1") (pinfunction "1_1") (pintype "bidirectional"))
    )
    (net (code "75") (name "unconnected-(BATERY_2-Pad2)") (class "Default")
      (node (ref "BATERY_2") (pin "2") (pinfunction "2_2") (pintype "bidirectional"))
    )
    (net (code "76") (name "unconnected-(BATERY_2-Pad4)") (class "Default")
      (node (ref "BATERY_2") (pin "4") (pinfunction "4_4") (pintype "bidirectional"))
    )
    (net (code "77") (name "unconnected-(BATERY_3-Pad1)") (class "Default")
      (node (ref "BATERY_3") (pin "1") (pinfunction "1_1") (pintype "bidirectional"))
    )
    (net (code "78") (name "unconnected-(BATERY_3-Pad2)") (class "Default")
      (node (ref "BATERY_3") (pin "2") (pinfunction "2_2") (pintype "bidirectional"))
    )
    (net (code "79") (name "unconnected-(BATERY_3-Pad4)") (class "Default")
      (node (ref "BATERY_3") (pin "4") (pinfunction "4_4") (pintype "bidirectional"))
    )
    (net (code "80") (name "unconnected-(JP9-Pad10)") (class "Default")
      (node (ref "JP9") (pin "10") (pinfunction "10_10") (pintype "passive"))
    )
    (net (code "81") (name "unconnected-(KICKER-Pad5)") (class "Default")
      (node (ref "KICKER") (pin "5") (pinfunction "5_5") (pintype "passive"))
    )
    (net (code "82") (name "unconnected-(LINE_SISTEM-Pad5)") (class "Default")
      (node (ref "LINE_SISTEM") (pin "5") (pinfunction "5_5") (pintype "passive"))
    )
    (net (code "83") (name "unconnected-(MAIN_POWER-3-ON-Pad3)") (class "Default")
      (node (ref "MAIN_POWER") (pin "3") (pinfunction "3-ON_3") (pintype "passive"))
    )
    (net (code "84") (name "unconnected-(MOTOR-3-ON-Pad3)") (class "Default")
      (node (ref "MOTOR") (pin "3") (pinfunction "3-ON_3") (pintype "passive"))
    )
    (net (code "85") (name "unconnected-(SMALL_LINE-Pad5)") (class "Default")
      (node (ref "SMALL_LINE") (pin "5") (pinfunction "5_5") (pintype "passive"))
    )
    (net (code "86") (name "unconnected-(U$4-PadCS)") (class "Default")
      (node (ref "U$4") (pin "CS") (pinfunction "CS_CS") (pintype "bidirectional"))
    )
    (net (code "87") (name "unconnected-(U$4-PadENA{slash}DIAGA)") (class "Default")
      (node (ref "U$4") (pin "ENA/DIAGA") (pinfunction "ENA/DIAGA_ENA/DIAGA") (pintype "bidirectional"))
    )
    (net (code "88") (name "unconnected-(U$4-PadENB{slash}DIAGB)") (class "Default")
      (node (ref "U$4") (pin "ENB/DIAGB") (pinfunction "ENB/DIAGB_ENB/DIAGB") (pintype "bidirectional"))
    )
    (net (code "89") (name "unconnected-(U$4-PadVOUT)") (class "Default")
      (node (ref "U$4") (pin "VOUT") (pinfunction "VOUT_VOUT") (pintype "bidirectional"))
    )
    (net (code "90") (name "unconnected-(U1-ADC6-Pad19)") (class "Default")
      (node (ref "U1") (pin "19") (pinfunction "ADC6_19") (pintype "bidirectional"))
    )
    (net (code "91") (name "unconnected-(U1-ADC7-Pad22)") (class "Default")
      (node (ref "U1") (pin "22") (pinfunction "ADC7_22") (pintype "bidirectional"))
    )
    (net (code "92") (name "unconnected-(U1-AREF-Pad20)") (class "Default")
      (node (ref "U1") (pin "20") (pinfunction "AREF_20") (pintype "bidirectional"))
    )
    (net (code "93") (name "unconnected-(U1-PB0(ICP)-Pad12)") (class "Default")
      (node (ref "U1") (pin "12") (pinfunction "PB0(ICP)_12") (pintype "bidirectional"))
    )
    (net (code "94") (name "unconnected-(U1-PB1(OC1A)-Pad13)") (class "Default")
      (node (ref "U1") (pin "13") (pinfunction "PB1(OC1A)_13") (pintype "bidirectional"))
    )
    (net (code "95") (name "unconnected-(U1-PC0(ADC0)-Pad23)") (class "Default")
      (node (ref "U1") (pin "23") (pinfunction "PC0(ADC0)_23") (pintype "bidirectional"))
    )
    (net (code "96") (name "unconnected-(U1-PC1(ADC1)-Pad24)") (class "Default")
      (node (ref "U1") (pin "24") (pinfunction "PC1(ADC1)_24") (pintype "bidirectional"))
    )
    (net (code "97") (name "unconnected-(U1-PC2(ADC2)-Pad25)") (class "Default")
      (node (ref "U1") (pin "25") (pinfunction "PC2(ADC2)_25") (pintype "bidirectional"))
    )
    (net (code "98") (name "unconnected-(U1-PC3(ADC3)-Pad26)") (class "Default")
      (node (ref "U1") (pin "26") (pinfunction "PC3(ADC3)_26") (pintype "bidirectional"))
    )
    (net (code "99") (name "unconnected-(U1-PC4(ADC4{slash}SDA)-Pad27)") (class "Default")
      (node (ref "U1") (pin "27") (pinfunction "PC4(ADC4/SDA)_27") (pintype "bidirectional"))
    )
    (net (code "100") (name "unconnected-(U1-PC5(ADC5{slash}SCL)-Pad28)") (class "Default")
      (node (ref "U1") (pin "28") (pinfunction "PC5(ADC5/SCL)_28") (pintype "bidirectional"))
    )
    (net (code "101") (name "unconnected-(U1-PD2(INT0)-Pad32)") (class "Default")
      (node (ref "U1") (pin "32") (pinfunction "PD2(INT0)_32") (pintype "bidirectional"))
    )
    (net (code "102") (name "unconnected-(U1-PD3(INT1)-Pad1)") (class "Default")
      (node (ref "U1") (pin "1") (pinfunction "PD3(INT1)_1") (pintype "bidirectional"))
    )
    (net (code "103") (name "unconnected-(U1-PD4(XCK{slash}T0)-Pad2)") (class "Default")
      (node (ref "U1") (pin "2") (pinfunction "PD4(XCK/T0)_2") (pintype "bidirectional"))
    )
    (net (code "104") (name "unconnected-(U2-ADC6-Pad19)") (class "Default")
      (node (ref "U2") (pin "19") (pinfunction "ADC6_19") (pintype "bidirectional"))
    )
    (net (code "105") (name "unconnected-(U2-ADC7-Pad22)") (class "Default")
      (node (ref "U2") (pin "22") (pinfunction "ADC7_22") (pintype "bidirectional"))
    )
    (net (code "106") (name "unconnected-(U2-AREF-Pad20)") (class "Default")
      (node (ref "U2") (pin "20") (pinfunction "AREF_20") (pintype "bidirectional"))
    )
    (net (code "107") (name "unconnected-(U2-PC1(ADC1)-Pad24)") (class "Default")
      (node (ref "U2") (pin "24") (pinfunction "PC1(ADC1)_24") (pintype "bidirectional"))
    )
    (net (code "108") (name "unconnected-(U2-PC2(ADC2)-Pad25)") (class "Default")
      (node (ref "U2") (pin "25") (pinfunction "PC2(ADC2)_25") (pintype "bidirectional"))
    )
    (net (code "109") (name "unconnected-(U2-PC3(ADC3)-Pad26)") (class "Default")
      (node (ref "U2") (pin "26") (pinfunction "PC3(ADC3)_26") (pintype "bidirectional"))
    )
    (net (code "110") (name "unconnected-(ULTRA_SISTEM-Pad5)") (class "Default")
      (node (ref "ULTRA_SISTEM") (pin "5") (pinfunction "5_5") (pintype "passive"))
    )
  )
)
